# Sheet1.net
KiCad netlist of a schematic drawn in Altium Designer
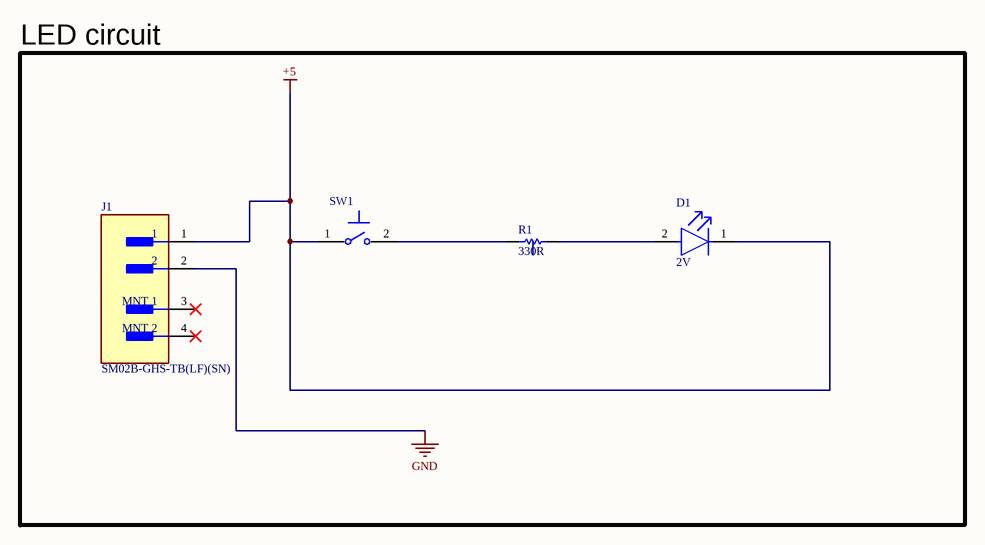
[diagram p0: Sheet1.SchDoc]

(export (version "E")
  (design (tool "Eeschema 10.0.6"))
  (components
    (comp (ref "D1")
      (value "2V")
      (footprint "FP-LTST-C190GKT-MFG")
      (description "LED GREEN CLEAR CHIP SMD")
      (libsource (lib "Altium Content Vault") (part "8706943c75ba83719d021d2fdc84c58"))
    )
    (comp (ref "J1")
      (value "SM02B-GHS-TB(LF)(SN)")
      (footprint "FP-SM02B-GHS-TB_LF_SN-MFG")
      (description "CONN HEADER SMD R/A 2POS 1.25MM")
      (libsource (lib "Altium Content Vault") (part "56ec3178a87b3978bdc1b3682cd516a"))
    )
    (comp (ref "R1")
      (value "330R")
      (footprint "RESC1608X55X25NL10T15")
      (description "Chip Resistor, 330 Ohm, +/- 1%, 0.1 W, -55 to 155 degC, 0603 (1608 Metric), RoHS, Tape and Reel")
      (fields (field (name "TOLERANCE") "10%"))
      (libsource (lib "Altium Content Vault") (part "RES-2"))
    )
    (comp (ref "SW1")
      (value "~")
      (footprint "FP-TL1015AF160QG-MFG")
      (description "SWITCH TACTILE SPST-NO 0.05A 12V")
      (libsource (lib "Altium Content Vault") (part "2041f8efb62e6aaa548c9fd35e2c2f1"))
    )
  )
  (nets
    (net (code "1") (name "+5") (class "Default")
      (node (ref "D1") (pin "1") (pinfunction "C_1") (pintype "passive"))
      (node (ref "J1") (pin "1") (pinfunction "1_1") (pintype "passive"))
      (node (ref "SW1") (pin "1") (pinfunction "1_1") (pintype "passive"))
    )
    (net (code "2") (name "GND") (class "Default")
      (node (ref "J1") (pin "2") (pinfunction "2_2") (pintype "passive"))
    )
    (net (code "3") (name "Net-(D1-A)") (class "Default")
      (node (ref "D1") (pin "2") (pinfunction "A_2") (pintype "passive"))
      (node (ref "R1") (pin "2") (pinfunction "2_2") (pintype "passive"))
    )
    (net (code "4") (name "Net-(R1-Pad1)") (class "Default")
      (node (ref "R1") (pin "1") (pinfunction "1_1") (pintype "passive"))
      (node (ref "SW1") (pin "2") (pinfunction "2_2") (pintype "passive"))
    )
    (net (code "5") (name "unconnected-(J1-MNT_1-Pad3)") (class "Default")
      (node (ref "J1") (pin "3") (pinfunction "MNT_1_3") (pintype "passive+no_connect"))
    )
    (net (code "6") (name "unconnected-(J1-MNT_2-Pad4)") (class "Default")
      (node (ref "J1") (pin "4") (pinfunction "MNT_2_4") (pintype "passive+no_connect"))
    )
  )
)
